# controller3.net
KiCad netlist of a schematic drawn in EAGLE
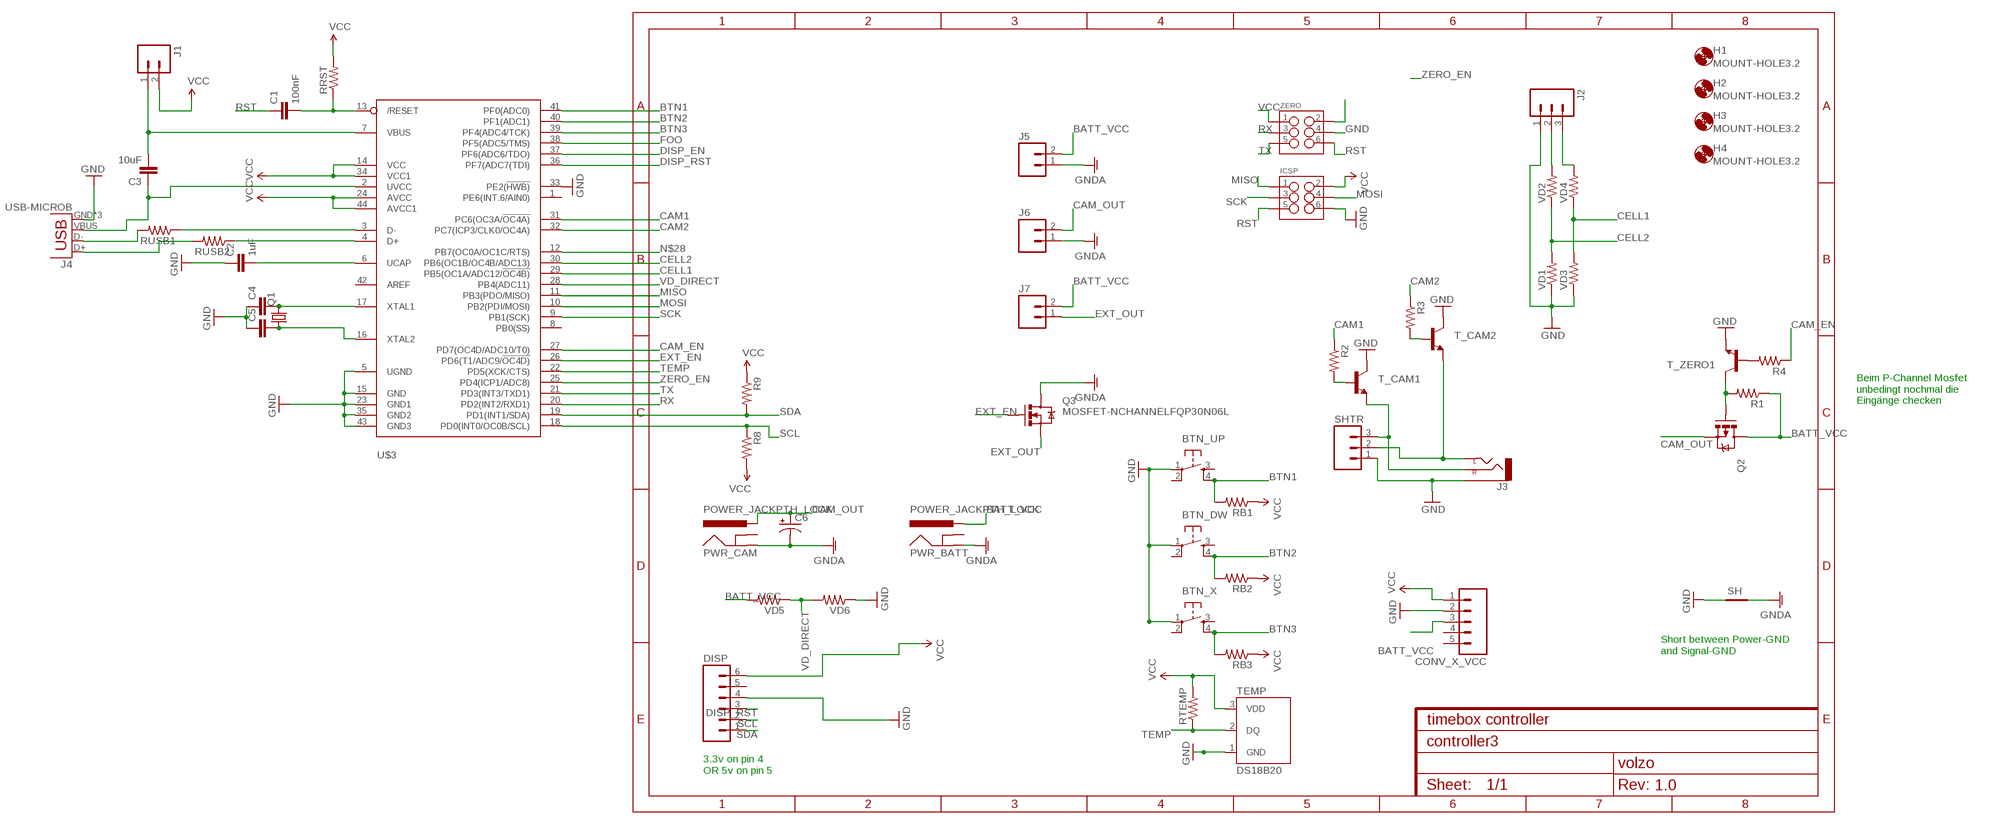
[diagram p0: schematic, sheet 1]

(export (version "E")
  (design (tool "Eeschema 10.0.6"))
  (components
    (comp (ref "BTN_DW")
      (value "TAC_SWITCHPTH")
      (footprint "eagle-import:TACTILE-PTH")
      (libsource (lib "eagle-import") (part "TAC_SWITCHPTH"))
    )
    (comp (ref "BTN_UP")
      (value "TAC_SWITCHPTH")
      (footprint "eagle-import:TACTILE-PTH")
      (libsource (lib "eagle-import") (part "TAC_SWITCHPTH"))
    )
    (comp (ref "BTN_X")
      (value "TAC_SWITCHPTH")
      (footprint "eagle-import:TACTILE-PTH")
      (libsource (lib "eagle-import") (part "TAC_SWITCHPTH"))
    )
    (comp (ref "C1")
      (value "100nF")
      (footprint "eagle-import:1206")
      (libsource (lib "eagle-import") (part "SparkFun-Passives_CAP1206"))
    )
    (comp (ref "C2")
      (value "1uF")
      (footprint "eagle-import:1206")
      (libsource (lib "eagle-import") (part "CAP1206"))
    )
    (comp (ref "C3")
      (value "10uF")
      (footprint "eagle-import:1206")
      (libsource (lib "eagle-import") (part "SparkFun-Passives_CAP1206"))
    )
    (comp (ref "C4")
      (value "CAP1206")
      (footprint "eagle-import:1206")
      (libsource (lib "eagle-import") (part "SparkFun-Passives_CAP1206"))
    )
    (comp (ref "C5")
      (value "CAP1206")
      (footprint "eagle-import:1206")
      (libsource (lib "eagle-import") (part "SparkFun-Passives_CAP1206"))
    )
    (comp (ref "C6")
      (value "CAP_POLPTH3")
      (footprint "eagle-import:CPOL-RADIAL-1000UF-63V")
      (libsource (lib "eagle-import") (part "CAP_POLPTH3"))
    )
    (comp (ref "CONV_X_VCC")
      (value "M05LOCK")
      (footprint "eagle-import:1X05_LOCK")
      (libsource (lib "eagle-import") (part "M05LOCK"))
    )
    (comp (ref "DISP")
      (value "M06FEMALE_LOCK")
      (footprint "eagle-import:1X06_FEMALE_LOCK.010")
      (libsource (lib "eagle-import") (part "M06FEMALE_LOCK"))
    )
    (comp (ref "H1")
      (value "MOUNT-HOLE3.2")
      (footprint "eagle-import:3,2")
      (libsource (lib "eagle-import") (part "MOUNT-HOLE3.2"))
    )
    (comp (ref "H2")
      (value "MOUNT-HOLE3.2")
      (footprint "eagle-import:3,2")
      (libsource (lib "eagle-import") (part "MOUNT-HOLE3.2"))
    )
    (comp (ref "H3")
      (value "MOUNT-HOLE3.2")
      (footprint "eagle-import:3,2")
      (libsource (lib "eagle-import") (part "MOUNT-HOLE3.2"))
    )
    (comp (ref "H4")
      (value "MOUNT-HOLE3.2")
      (footprint "eagle-import:3,2")
      (libsource (lib "eagle-import") (part "MOUNT-HOLE3.2"))
    )
    (comp (ref "ICSP")
      (value "M03X2FEMALE")
      (footprint "eagle-import:2X3")
      (libsource (lib "eagle-import") (part "M03X2FEMALE"))
    )
    (comp (ref "J1")
      (value "M02LOCK")
      (footprint "eagle-import:1X02_LOCK")
      (libsource (lib "eagle-import") (part "M02LOCK"))
    )
    (comp (ref "J2")
      (value "M03LOCK")
      (footprint "eagle-import:1X03_LOCK")
      (libsource (lib "eagle-import") (part "M03LOCK"))
    )
    (comp (ref "J3")
      (value "AUDIO-JACK2.5MM")
      (footprint "eagle-import:STEREOJACK2.5MM_STEREOJACK2.5MM")
      (libsource (lib "eagle-import") (part "AUDIO-JACK2.5MM"))
    )
    (comp (ref "J4")
      (value "USB-MICROB")
      (footprint "eagle-import:USB-MICROB")
      (libsource (lib "eagle-import") (part "USB-MICROB"))
    )
    (comp (ref "J5")
      (value "M025MM")
      (footprint "eagle-import:SCREWTERMINAL-5MM-2")
      (libsource (lib "eagle-import") (part "M025MM"))
    )
    (comp (ref "J6")
      (value "M025MM")
      (footprint "eagle-import:SCREWTERMINAL-5MM-2")
      (libsource (lib "eagle-import") (part "M025MM"))
    )
    (comp (ref "J7")
      (value "M025MM")
      (footprint "eagle-import:SCREWTERMINAL-5MM-2")
      (libsource (lib "eagle-import") (part "M025MM"))
    )
    (comp (ref "PWR_BATT")
      (value "POWER_JACKPTH_LOCK")
      (footprint "eagle-import:POWER_JACK_PTH_LOCK")
      (libsource (lib "eagle-import") (part "POWER_JACKPTH_LOCK"))
    )
    (comp (ref "PWR_CAM")
      (value "POWER_JACKPTH_LOCK")
      (footprint "eagle-import:POWER_JACK_PTH_LOCK")
      (libsource (lib "eagle-import") (part "POWER_JACKPTH_LOCK"))
    )
    (comp (ref "Q1")
      (value "CRYSTALHC49S")
      (footprint "eagle-import:HC49_S")
      (libsource (lib "eagle-import") (part "CRYSTALHC49S"))
    )
    (comp (ref "Q2")
      (value "MOSFET-PCHANNELFQP27P06")
      (footprint "eagle-import:TO220V")
      (libsource (lib "eagle-import") (part "MOSFET-PCHANNELFQP27P06"))
    )
    (comp (ref "Q3")
      (value "MOSFET-NCHANNELFQP30N06L")
      (footprint "eagle-import:TO220V")
      (libsource (lib "eagle-import") (part "MOSFET-NCHANNELFQP30N06L"))
    )
    (comp (ref "R1")
      (value "RESISTOR1206")
      (footprint "eagle-import:1206")
      (libsource (lib "eagle-import") (part "RESISTOR1206"))
    )
    (comp (ref "R2")
      (value "RESISTOR1206")
      (footprint "eagle-import:1206")
      (libsource (lib "eagle-import") (part "RESISTOR1206"))
    )
    (comp (ref "R3")
      (value "RESISTOR1206")
      (footprint "eagle-import:1206")
      (libsource (lib "eagle-import") (part "RESISTOR1206"))
    )
    (comp (ref "R4")
      (value "RESISTOR1206")
      (footprint "eagle-import:1206")
      (libsource (lib "eagle-import") (part "RESISTOR1206"))
    )
    (comp (ref "R8")
      (value "RESISTOR1206")
      (footprint "eagle-import:1206")
      (libsource (lib "eagle-import") (part "RESISTOR1206"))
    )
    (comp (ref "R9")
      (value "RESISTOR1206")
      (footprint "eagle-import:1206")
      (libsource (lib "eagle-import") (part "RESISTOR1206"))
    )
    (comp (ref "RB1")
      (value "RESISTOR1206")
      (footprint "eagle-import:1206")
      (libsource (lib "eagle-import") (part "RESISTOR1206"))
    )
    (comp (ref "RB2")
      (value "RESISTOR1206")
      (footprint "eagle-import:1206")
      (libsource (lib "eagle-import") (part "RESISTOR1206"))
    )
    (comp (ref "RB3")
      (value "RESISTOR1206")
      (footprint "eagle-import:1206")
      (libsource (lib "eagle-import") (part "RESISTOR1206"))
    )
    (comp (ref "RRST")
      (value "RESISTOR1206")
      (footprint "eagle-import:1206")
      (libsource (lib "eagle-import") (part "RESISTOR1206"))
    )
    (comp (ref "RTEMP")
      (value "RESISTOR1206")
      (footprint "eagle-import:1206")
      (libsource (lib "eagle-import") (part "RESISTOR1206"))
    )
    (comp (ref "RUSB1")
      (value "RESISTOR1206")
      (footprint "eagle-import:1206")
      (libsource (lib "eagle-import") (part "RESISTOR1206"))
    )
    (comp (ref "RUSB2")
      (value "RESISTOR1206")
      (footprint "eagle-import:1206")
      (libsource (lib "eagle-import") (part "RESISTOR1206"))
    )
    (comp (ref "SH")
      (value "SHORT-HT5")
      (footprint "eagle-import:SHORT_TOP-50")
      (libsource (lib "eagle-import") (part "SHORT-HT5"))
    )
    (comp (ref "SHTR")
      (value "M03LOCK")
      (footprint "eagle-import:1X03_LOCK")
      (libsource (lib "eagle-import") (part "M03LOCK"))
    )
    (comp (ref "TEMP")
      (value "DS18B20")
      (footprint "eagle-import:TO-92-AMMO")
      (libsource (lib "eagle-import") (part "DS18B20"))
    )
    (comp (ref "T_CAM1")
      (value "TRANSISTOR_NPN2N3904")
      (footprint "eagle-import:TO-92")
      (libsource (lib "eagle-import") (part "TRANSISTOR_NPN2N3904"))
    )
    (comp (ref "T_CAM2")
      (value "TRANSISTOR_NPN2N3904")
      (footprint "eagle-import:TO-92")
      (libsource (lib "eagle-import") (part "TRANSISTOR_NPN2N3904"))
    )
    (comp (ref "T_ZERO1")
      (value "TRANSISTOR_NPN2N3904")
      (footprint "eagle-import:TO-92")
      (libsource (lib "eagle-import") (part "TRANSISTOR_NPN2N3904"))
    )
    (comp (ref "U$3")
      (value "ATMEGA32U4-AU")
      (footprint "eagle-import:TQFP44")
      (libsource (lib "eagle-import") (part "ATMEGA32U4-AU"))
    )
    (comp (ref "VD1")
      (value "RESISTOR1206")
      (footprint "eagle-import:1206")
      (libsource (lib "eagle-import") (part "RESISTOR1206"))
    )
    (comp (ref "VD2")
      (value "RESISTOR1206")
      (footprint "eagle-import:1206")
      (libsource (lib "eagle-import") (part "RESISTOR1206"))
    )
    (comp (ref "VD3")
      (value "RESISTOR1206")
      (footprint "eagle-import:1206")
      (libsource (lib "eagle-import") (part "RESISTOR1206"))
    )
    (comp (ref "VD4")
      (value "RESISTOR1206")
      (footprint "eagle-import:1206")
      (libsource (lib "eagle-import") (part "RESISTOR1206"))
    )
    (comp (ref "VD5")
      (value "RESISTOR1206")
      (footprint "eagle-import:1206")
      (libsource (lib "eagle-import") (part "RESISTOR1206"))
    )
    (comp (ref "VD6")
      (value "RESISTOR1206")
      (footprint "eagle-import:1206")
      (libsource (lib "eagle-import") (part "RESISTOR1206"))
    )
    (comp (ref "ZERO")
      (value "M03X2FEMALE")
      (footprint "eagle-import:2X3")
      (libsource (lib "eagle-import") (part "M03X2FEMALE"))
    )
  )
  (nets
    (net (code "1") (name "/BATT_VCC") (class "Default")
      (node (ref "CONV_X_VCC") (pin "3") (pinfunction "3_3") (pintype "passive"))
      (node (ref "J5") (pin "2") (pinfunction "2_2") (pintype "passive"))
      (node (ref "J7") (pin "2") (pinfunction "2_2") (pintype "passive"))
      (node (ref "PWR_BATT") (pin "PWR") (pinfunction "PWR_PWR") (pintype "bidirectional"))
      (node (ref "Q2") (pin "2") (pinfunction "D_2") (pintype "passive"))
      (node (ref "R1") (pin "1") (pinfunction "1_1") (pintype "passive"))
      (node (ref "VD5") (pin "2") (pinfunction "2_2") (pintype "passive"))
    )
    (net (code "2") (name "/BTN1") (class "Default")
      (node (ref "BTN_UP") (pin "4") (pinfunction "4_4") (pintype "passive"))
      (node (ref "RB1") (pin "2") (pinfunction "2_2") (pintype "passive"))
      (node (ref "U$3") (pin "41") (pinfunction "PF0(ADC0)_41") (pintype "bidirectional"))
    )
    (net (code "3") (name "/BTN2") (class "Default")
      (node (ref "BTN_DW") (pin "4") (pinfunction "4_4") (pintype "passive"))
      (node (ref "RB2") (pin "2") (pinfunction "2_2") (pintype "passive"))
      (node (ref "U$3") (pin "40") (pinfunction "PF1(ADC1)_40") (pintype "bidirectional"))
    )
    (net (code "4") (name "/BTN3") (class "Default")
      (node (ref "BTN_X") (pin "4") (pinfunction "4_4") (pintype "passive"))
      (node (ref "RB3") (pin "2") (pinfunction "2_2") (pintype "passive"))
      (node (ref "U$3") (pin "39") (pinfunction "PF4(ADC4/TCK)_39") (pintype "bidirectional"))
    )
    (net (code "5") (name "/CAM1") (class "Default")
      (node (ref "R2") (pin "1") (pinfunction "1_1") (pintype "passive"))
      (node (ref "U$3") (pin "31") (pinfunction "PC6(OC3A/~{OC4A})_31") (pintype "bidirectional"))
    )
    (net (code "6") (name "/CAM2") (class "Default")
      (node (ref "R3") (pin "1") (pinfunction "1_1") (pintype "passive"))
      (node (ref "U$3") (pin "32") (pinfunction "PC7(ICP3/CLK0/OC4A)_32") (pintype "bidirectional"))
    )
    (net (code "7") (name "/CAM_EN") (class "Default")
      (node (ref "R4") (pin "1") (pinfunction "1_1") (pintype "passive"))
      (node (ref "U$3") (pin "27") (pinfunction "PD7(OC4D/ADC10/T0)_27") (pintype "bidirectional"))
    )
    (net (code "8") (name "/CAM_OUT") (class "Default")
      (node (ref "C6") (pin "1") (pinfunction "+_1") (pintype "passive"))
      (node (ref "J6") (pin "2") (pinfunction "2_2") (pintype "passive"))
      (node (ref "PWR_CAM") (pin "PWR") (pinfunction "PWR_PWR") (pintype "bidirectional"))
      (node (ref "Q2") (pin "3") (pinfunction "S_3") (pintype "passive"))
    )
    (net (code "9") (name "/CELL1") (class "Default")
      (node (ref "U$3") (pin "29") (pinfunction "PB5(OC1A/ADC12/~{OC4B})_29") (pintype "bidirectional"))
      (node (ref "VD3") (pin "2") (pinfunction "2_2") (pintype "passive"))
      (node (ref "VD4") (pin "1") (pinfunction "1_1") (pintype "passive"))
    )
    (net (code "10") (name "/CELL2") (class "Default")
      (node (ref "U$3") (pin "30") (pinfunction "PB6(OC1B/OC4B/ADC13)_30") (pintype "bidirectional"))
      (node (ref "VD1") (pin "2") (pinfunction "2_2") (pintype "passive"))
      (node (ref "VD2") (pin "1") (pinfunction "1_1") (pintype "passive"))
    )
    (net (code "11") (name "/DISP_EN") (class "Default")
      (node (ref "U$3") (pin "37") (pinfunction "PF6(ADC6/TDO)_37") (pintype "bidirectional"))
    )
    (net (code "12") (name "/DISP_RST") (class "Default")
      (node (ref "DISP") (pin "3") (pinfunction "3_3") (pintype "passive"))
      (node (ref "U$3") (pin "36") (pinfunction "PF7(ADC7(TDI)_36") (pintype "bidirectional"))
    )
    (net (code "13") (name "/EXT_EN") (class "Default")
      (node (ref "Q3") (pin "1") (pinfunction "G_1") (pintype "passive"))
      (node (ref "U$3") (pin "26") (pinfunction "PD6(T1/ADC9/~{OC4D})_26") (pintype "bidirectional"))
    )
    (net (code "14") (name "/EXT_OUT") (class "Default")
      (node (ref "J7") (pin "1") (pinfunction "1_1") (pintype "passive"))
      (node (ref "Q3") (pin "3") (pinfunction "S_3") (pintype "passive"))
    )
    (net (code "15") (name "/FOO") (class "Default")
      (node (ref "U$3") (pin "38") (pinfunction "PF5(ADC5/TMS)_38") (pintype "bidirectional"))
    )
    (net (code "16") (name "/MISO") (class "Default")
      (node (ref "ICSP") (pin "1") (pinfunction "1_1") (pintype "bidirectional"))
      (node (ref "U$3") (pin "11") (pinfunction "PB3(PDO/MISO)_11") (pintype "bidirectional"))
    )
    (net (code "17") (name "/MOSI") (class "Default")
      (node (ref "ICSP") (pin "4") (pinfunction "4_4") (pintype "bidirectional"))
      (node (ref "U$3") (pin "10") (pinfunction "PB2(PDI/MOSI)_10") (pintype "bidirectional"))
    )
    (net (code "18") (name "/N$28") (class "Default")
      (node (ref "U$3") (pin "12") (pinfunction "PB7(OC0A/OC1C/RTS)_12") (pintype "bidirectional"))
    )
    (net (code "19") (name "/RST") (class "Default")
      (node (ref "C1") (pin "1") (pinfunction "1_1") (pintype "passive"))
      (node (ref "ICSP") (pin "5") (pinfunction "5_5") (pintype "bidirectional"))
      (node (ref "ZERO") (pin "6") (pinfunction "6_6") (pintype "bidirectional"))
    )
    (net (code "20") (name "/RX") (class "Default")
      (node (ref "U$3") (pin "20") (pinfunction "PD2(INT2/RXD1)_20") (pintype "bidirectional"))
      (node (ref "ZERO") (pin "3") (pinfunction "3_3") (pintype "bidirectional"))
    )
    (net (code "21") (name "/SCK") (class "Default")
      (node (ref "ICSP") (pin "3") (pinfunction "3_3") (pintype "bidirectional"))
      (node (ref "U$3") (pin "9") (pinfunction "PB1(SCK)_9") (pintype "bidirectional"))
    )
    (net (code "22") (name "/SCL") (class "Default")
      (node (ref "DISP") (pin "2") (pinfunction "2_2") (pintype "passive"))
      (node (ref "R8") (pin "1") (pinfunction "1_1") (pintype "passive"))
      (node (ref "U$3") (pin "18") (pinfunction "PD0(INT0/OC0B/SCL)_18") (pintype "bidirectional"))
    )
    (net (code "23") (name "/SDA") (class "Default")
      (node (ref "DISP") (pin "1") (pinfunction "1_1") (pintype "passive"))
      (node (ref "R9") (pin "2") (pinfunction "2_2") (pintype "passive"))
      (node (ref "U$3") (pin "19") (pinfunction "PD1(INT1/SDA)_19") (pintype "bidirectional"))
    )
    (net (code "24") (name "/TEMP") (class "Default")
      (node (ref "RTEMP") (pin "1") (pinfunction "1_1") (pintype "passive"))
      (node (ref "TEMP") (pin "2") (pinfunction "DQ_2") (pintype "bidirectional"))
      (node (ref "U$3") (pin "22") (pinfunction "PD5(XCK/CTS)_22") (pintype "bidirectional"))
    )
    (net (code "25") (name "/TX") (class "Default")
      (node (ref "U$3") (pin "21") (pinfunction "PD3(INT3/TXD1)_21") (pintype "bidirectional"))
      (node (ref "ZERO") (pin "5") (pinfunction "5_5") (pintype "bidirectional"))
    )
    (net (code "26") (name "/VD_DIRECT") (class "Default")
      (node (ref "U$3") (pin "28") (pinfunction "PB4(ADC11)_28") (pintype "bidirectional"))
      (node (ref "VD5") (pin "1") (pinfunction "1_1") (pintype "passive"))
      (node (ref "VD6") (pin "2") (pinfunction "2_2") (pintype "passive"))
    )
    (net (code "27") (name "/ZERO_EN") (class "Default")
      (node (ref "U$3") (pin "25") (pinfunction "PD4(ICP1/ADC8)_25") (pintype "bidirectional"))
    )
    (net (code "28") (name "GND") (class "Default")
      (node (ref "BTN_DW") (pin "1") (pinfunction "1_1") (pintype "passive"))
      (node (ref "BTN_UP") (pin "1") (pinfunction "1_1") (pintype "passive"))
      (node (ref "BTN_X") (pin "1") (pinfunction "1_1") (pintype "passive"))
      (node (ref "C2") (pin "1") (pinfunction "1_1") (pintype "passive"))
      (node (ref "C4") (pin "1") (pinfunction "1_1") (pintype "passive"))
      (node (ref "C5") (pin "1") (pinfunction "1_1") (pintype "passive"))
      (node (ref "CONV_X_VCC") (pin "2") (pinfunction "2_2") (pintype "passive"))
      (node (ref "DISP") (pin "4") (pinfunction "4_4") (pintype "passive"))
      (node (ref "ICSP") (pin "6") (pinfunction "6_6") (pintype "bidirectional"))
      (node (ref "J2") (pin "1") (pinfunction "1_1") (pintype "passive"))
      (node (ref "J3") (pin "SHIELD") (pinfunction "SLEEVE_SHIELD") (pintype "bidirectional"))
      (node (ref "J4") (pin "GND") (pinfunction "GND_GND") (pintype "bidirectional"))
      (node (ref "J4") (pin "MT1") (pinfunction "GND_MT1") (pintype "bidirectional"))
      (node (ref "J4") (pin "MT2") (pinfunction "GND_MT2") (pintype "bidirectional"))
      (node (ref "SH") (pin "1") (pinfunction "P$1_1") (pintype "bidirectional"))
      (node (ref "SHTR") (pin "1") (pinfunction "1_1") (pintype "passive"))
      (node (ref "TEMP") (pin "1") (pinfunction "GND_1") (pintype "power_in"))
      (node (ref "T_CAM1") (pin "3") (pinfunction "C_3") (pintype "passive"))
      (node (ref "T_CAM2") (pin "3") (pinfunction "C_3") (pintype "passive"))
      (node (ref "T_ZERO1") (pin "1") (pinfunction "E_1") (pintype "passive"))
      (node (ref "U$3") (pin "15") (pinfunction "GND_15") (pintype "bidirectional"))
      (node (ref "U$3") (pin "23") (pinfunction "GND1_23") (pintype "bidirectional"))
      (node (ref "U$3") (pin "33") (pinfunction "PE2(~{HWB})_33") (pintype "bidirectional"))
      (node (ref "U$3") (pin "35") (pinfunction "GND2_35") (pintype "bidirectional"))
      (node (ref "U$3") (pin "43") (pinfunction "GND3_43") (pintype "bidirectional"))
      (node (ref "U$3") (pin "5") (pinfunction "UGND_5") (pintype "bidirectional"))
      (node (ref "VD1") (pin "1") (pinfunction "1_1") (pintype "passive"))
      (node (ref "VD3") (pin "1") (pinfunction "1_1") (pintype "passive"))
      (node (ref "VD6") (pin "1") (pinfunction "1_1") (pintype "passive"))
      (node (ref "ZERO") (pin "4") (pinfunction "4_4") (pintype "bidirectional"))
    )
    (net (code "29") (name "GNDA") (class "Default")
      (node (ref "C6") (pin "2") (pinfunction "-_2") (pintype "passive"))
      (node (ref "J5") (pin "1") (pinfunction "1_1") (pintype "passive"))
      (node (ref "J6") (pin "1") (pinfunction "1_1") (pintype "passive"))
      (node (ref "PWR_BATT") (pin "GND") (pinfunction "GND_GND") (pintype "bidirectional"))
      (node (ref "PWR_CAM") (pin "GND") (pinfunction "GND_GND") (pintype "bidirectional"))
      (node (ref "Q3") (pin "2") (pinfunction "D_2") (pintype "passive"))
      (node (ref "SH") (pin "2") (pinfunction "P$2_2") (pintype "bidirectional"))
    )
    (net (code "30") (name "Net-(J2-Pad2)") (class "Default")
      (node (ref "J2") (pin "2") (pinfunction "2_2") (pintype "passive"))
      (node (ref "VD2") (pin "2") (pinfunction "2_2") (pintype "passive"))
    )
    (net (code "31") (name "Net-(J2-Pad3)") (class "Default")
      (node (ref "J2") (pin "3") (pinfunction "3_3") (pintype "passive"))
      (node (ref "VD4") (pin "2") (pinfunction "2_2") (pintype "passive"))
    )
    (net (code "32") (name "Net-(J3-LEFT)") (class "Default")
      (node (ref "J3") (pin "TIP") (pinfunction "LEFT_TIP") (pintype "bidirectional"))
      (node (ref "SHTR") (pin "2") (pinfunction "2_2") (pintype "passive"))
      (node (ref "T_CAM2") (pin "1") (pinfunction "E_1") (pintype "passive"))
    )
    (net (code "33") (name "Net-(J3-RIGHT)") (class "Default")
      (node (ref "J3") (pin "RING") (pinfunction "RIGHT_RING") (pintype "bidirectional"))
      (node (ref "SHTR") (pin "3") (pinfunction "3_3") (pintype "passive"))
      (node (ref "T_CAM1") (pin "1") (pinfunction "E_1") (pintype "passive"))
    )
    (net (code "34") (name "Net-(J4-PadD+)") (class "Default")
      (node (ref "J4") (pin "D+") (pinfunction "D+_D+") (pintype "bidirectional"))
      (node (ref "RUSB2") (pin "2") (pinfunction "2_2") (pintype "passive"))
    )
    (net (code "35") (name "Net-(J4-PadD-)") (class "Default")
      (node (ref "J4") (pin "D-") (pinfunction "D-_D-") (pintype "bidirectional"))
      (node (ref "RUSB1") (pin "2") (pinfunction "2_2") (pintype "passive"))
    )
    (net (code "36") (name "Net-(Q2-G)") (class "Default")
      (node (ref "Q2") (pin "1") (pinfunction "G_1") (pintype "passive"))
      (node (ref "R1") (pin "2") (pinfunction "2_2") (pintype "passive"))
      (node (ref "T_ZERO1") (pin "3") (pinfunction "C_3") (pintype "passive"))
    )
    (net (code "37") (name "Net-(T_CAM1-B)") (class "Default")
      (node (ref "R2") (pin "2") (pinfunction "2_2") (pintype "passive"))
      (node (ref "T_CAM1") (pin "2") (pinfunction "B_2") (pintype "passive"))
    )
    (net (code "38") (name "Net-(T_CAM2-B)") (class "Default")
      (node (ref "R3") (pin "2") (pinfunction "2_2") (pintype "passive"))
      (node (ref "T_CAM2") (pin "2") (pinfunction "B_2") (pintype "passive"))
    )
    (net (code "39") (name "Net-(T_ZERO1-B)") (class "Default")
      (node (ref "R4") (pin "2") (pinfunction "2_2") (pintype "passive"))
      (node (ref "T_ZERO1") (pin "2") (pinfunction "B_2") (pintype "passive"))
    )
    (net (code "40") (name "Net-(U$3-D+)") (class "Default")
      (node (ref "RUSB2") (pin "1") (pinfunction "1_1") (pintype "passive"))
      (node (ref "U$3") (pin "4") (pinfunction "D+_4") (pintype "bidirectional"))
    )
    (net (code "41") (name "Net-(U$3-D-)") (class "Default")
      (node (ref "RUSB1") (pin "1") (pinfunction "1_1") (pintype "passive"))
      (node (ref "U$3") (pin "3") (pinfunction "D-_3") (pintype "bidirectional"))
    )
    (net (code "42") (name "Net-(U$3-UCAP)") (class "Default")
      (node (ref "C2") (pin "2") (pinfunction "2_2") (pintype "passive"))
      (node (ref "U$3") (pin "6") (pinfunction "UCAP_6") (pintype "bidirectional"))
    )
    (net (code "43") (name "Net-(U$3-UVCC)") (class "Default")
      (node (ref "C3") (pin "1") (pinfunction "1_1") (pintype "passive"))
      (node (ref "J4") (pin "VBUS") (pinfunction "VBUS_VBUS") (pintype "bidirectional"))
      (node (ref "U$3") (pin "2") (pinfunction "UVCC_2") (pintype "bidirectional"))
    )
    (net (code "44") (name "Net-(U$3-VBUS)") (class "Default")
      (node (ref "C3") (pin "2") (pinfunction "2_2") (pintype "passive"))
      (node (ref "J1") (pin "1") (pinfunction "1_1") (pintype "passive"))
      (node (ref "U$3") (pin "7") (pinfunction "VBUS_7") (pintype "bidirectional"))
    )
    (net (code "45") (name "Net-(U$3-XTAL1)") (class "Default")
      (node (ref "C4") (pin "2") (pinfunction "2_2") (pintype "passive"))
      (node (ref "Q1") (pin "2") (pinfunction "2_2") (pintype "passive"))
      (node (ref "U$3") (pin "17") (pinfunction "XTAL1_17") (pintype "bidirectional"))
    )
    (net (code "46") (name "Net-(U$3-XTAL2)") (class "Default")
      (node (ref "C5") (pin "2") (pinfunction "2_2") (pintype "passive"))
      (node (ref "Q1") (pin "1") (pinfunction "1_1") (pintype "passive"))
      (node (ref "U$3") (pin "16") (pinfunction "XTAL2_16") (pintype "bidirectional"))
    )
    (net (code "47") (name "Net-(U$3-{slash}RESET)") (class "Default")
      (node (ref "C1") (pin "2") (pinfunction "2_2") (pintype "passive"))
      (node (ref "RRST") (pin "1") (pinfunction "1_1") (pintype "passive"))
      (node (ref "U$3") (pin "13") (pinfunction "/RESET_13") (pintype "bidirectional"))
    )
    (net (code "48") (name "VCC") (class "Default")
      (node (ref "CONV_X_VCC") (pin "1") (pinfunction "1_1") (pintype "passive"))
      (node (ref "DISP") (pin "6") (pinfunction "6_6") (pintype "passive"))
      (node (ref "ICSP") (pin "2") (pinfunction "2_2") (pintype "bidirectional"))
      (node (ref "J1") (pin "2") (pinfunction "2_2") (pintype "passive"))
      (node (ref "R8") (pin "2") (pinfunction "2_2") (pintype "passive"))
      (node (ref "R9") (pin "1") (pinfunction "1_1") (pintype "passive"))
      (node (ref "RB1") (pin "1") (pinfunction "1_1") (pintype "passive"))
      (node (ref "RB2") (pin "1") (pinfunction "1_1") (pintype "passive"))
      (node (ref "RB3") (pin "1") (pinfunction "1_1") (pintype "passive"))
      (node (ref "RRST") (pin "2") (pinfunction "2_2") (pintype "passive"))
      (node (ref "RTEMP") (pin "2") (pinfunction "2_2") (pintype "passive"))
      (node (ref "TEMP") (pin "3") (pinfunction "VDD_3") (pintype "power_in"))
      (node (ref "U$3") (pin "14") (pinfunction "VCC_14") (pintype "bidirectional"))
      (node (ref "U$3") (pin "24") (pinfunction "AVCC_24") (pintype "bidirectional"))
      (node (ref "U$3") (pin "34") (pinfunction "VCC1_34") (pintype "bidirectional"))
      (node (ref "U$3") (pin "44") (pinfunction "AVCC1_44") (pintype "bidirectional"))
      (node (ref "ZERO") (pin "1") (pinfunction "1_1") (pintype "bidirectional"))
    )
    (net (code "49") (name "unconnected-(BTN_DW-Pad2)") (class "Default")
      (node (ref "BTN_DW") (pin "2") (pinfunction "2_2") (pintype "passive"))
    )
    (net (code "50") (name "unconnected-(BTN_DW-Pad3)") (class "Default")
      (node (ref "BTN_DW") (pin "3") (pinfunction "3_3") (pintype "passive"))
    )
    (net (code "51") (name "unconnected-(BTN_UP-Pad2)") (class "Default")
      (node (ref "BTN_UP") (pin "2") (pinfunction "2_2") (pintype "passive"))
    )
    (net (code "52") (name "unconnected-(BTN_UP-Pad3)") (class "Default")
      (node (ref "BTN_UP") (pin "3") (pinfunction "3_3") (pintype "passive"))
    )
    (net (code "53") (name "unconnected-(BTN_X-Pad2)") (class "Default")
      (node (ref "BTN_X") (pin "2") (pinfunction "2_2") (pintype "passive"))
    )
    (net (code "54") (name "unconnected-(BTN_X-Pad3)") (class "Default")
      (node (ref "BTN_X") (pin "3") (pinfunction "3_3") (pintype "passive"))
    )
    (net (code "55") (name "unconnected-(CONV_X_VCC-Pad4)") (class "Default")
      (node (ref "CONV_X_VCC") (pin "4") (pinfunction "4_4") (pintype "passive"))
    )
    (net (code "56") (name "unconnected-(CONV_X_VCC-Pad5)") (class "Default")
      (node (ref "CONV_X_VCC") (pin "5") (pinfunction "5_5") (pintype "passive"))
    )
    (net (code "57") (name "unconnected-(DISP-Pad5)") (class "Default")
      (node (ref "DISP") (pin "5") (pinfunction "5_5") (pintype "passive"))
    )
    (net (code "58") (name "unconnected-(PWR_BATT-PadGNDBREAK)") (class "Default")
      (node (ref "PWR_BATT") (pin "GNDBREAK") (pinfunction "GNDBREAK_GNDBREAK") (pintype "bidirectional"))
    )
    (net (code "59") (name "unconnected-(PWR_CAM-PadGNDBREAK)") (class "Default")
      (node (ref "PWR_CAM") (pin "GNDBREAK") (pinfunction "GNDBREAK_GNDBREAK") (pintype "bidirectional"))
    )
    (net (code "60") (name "unconnected-(U$3-AREF-Pad42)") (class "Default")
      (node (ref "U$3") (pin "42") (pinfunction "AREF_42") (pintype "bidirectional"))
    )
    (net (code "61") (name "unconnected-(U$3-PB0(SS)-Pad8)") (class "Default")
      (node (ref "U$3") (pin "8") (pinfunction "PB0(SS)_8") (pintype "bidirectional"))
    )
    (net (code "62") (name "unconnected-(U$3-PE6(INT.6{slash}AIN0)-Pad1)") (class "Default")
      (node (ref "U$3") (pin "1") (pinfunction "PE6(INT.6/AIN0)_1") (pintype "bidirectional"))
    )
    (net (code "63") (name "unconnected-(ZERO-Pad2)") (class "Default")
      (node (ref "ZERO") (pin "2") (pinfunction "2_2") (pintype "bidirectional"))
    )
  )
)
